# Charge_Amp_Schematic.net
KiCad netlist of a schematic drawn in Altium Designer
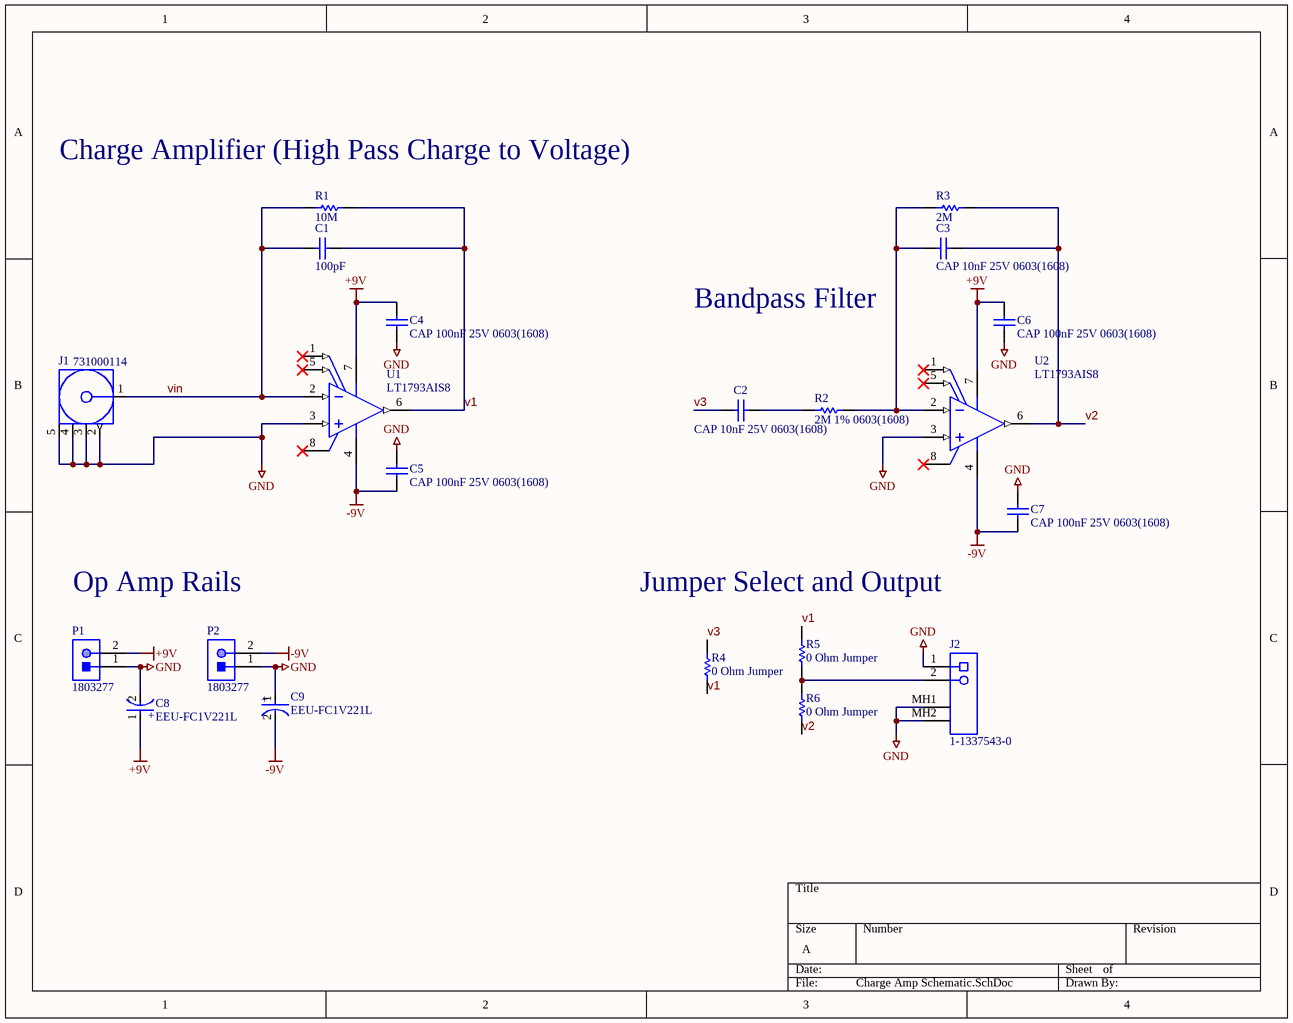
[diagram p0: Charge Amp Schematic.SchDoc]

(export (version "E")
  (design (tool "Eeschema 10.0.6"))
  (components
    (comp (ref "C1")
      (value "100pF")
      (footprint "CAPC0603(1608)100_M")
      (fields (field (name "TOLERANCE") "Â±5%"))
      (libsource (lib "Altium Content Vault") (part "CAP"))
    )
    (comp (ref "C2")
      (value "CAP 10nF 25V 0603(1608)")
      (footprint "CAPC0603(1608)100_M")
      (description "CAP 10nF 25V ±5% 0603 (1608 Metric) Thickness 1mm SMD")
      (fields (field (name "TOLERANCE") "Â±5%"))
      (libsource (lib "Altium Content Vault") (part "CAP"))
    )
    (comp (ref "C3")
      (value "CAP 10nF 25V 0603(1608)")
      (footprint "CAPC0603(1608)100_M")
      (description "CAP 10nF 25V ±5% 0603 (1608 Metric) Thickness 1mm SMD")
      (fields (field (name "TOLERANCE") "Â±5%"))
      (libsource (lib "Altium Content Vault") (part "CAP"))
    )
    (comp (ref "C4")
      (value "CAP 100nF 25V 0603(1608)")
      (footprint "CAPC0603(1608)100_N")
      (description "CAP 100nF 25V ±5% 0603 (1608 Metric) Thickness 1mm SMD")
      (fields (field (name "TOLERANCE") "Â±5%"))
      (libsource (lib "Altium Content Vault") (part "CAP"))
    )
    (comp (ref "C5")
      (value "CAP 100nF 25V 0603(1608)")
      (footprint "CAPC0603(1608)100_N")
      (description "CAP 100nF 25V ±5% 0603 (1608 Metric) Thickness 1mm SMD")
      (fields (field (name "TOLERANCE") "Â±5%"))
      (libsource (lib "Altium Content Vault") (part "CAP"))
    )
    (comp (ref "C6")
      (value "CAP 100nF 25V 0603(1608)")
      (footprint "CAPC0603(1608)100_N")
      (description "CAP 100nF 25V ±5% 0603 (1608 Metric) Thickness 1mm SMD")
      (fields (field (name "TOLERANCE") "Â±5%"))
      (libsource (lib "Altium Content Vault") (part "CAP"))
    )
    (comp (ref "C7")
      (value "CAP 100nF 25V 0603(1608)")
      (footprint "CAPC0603(1608)100_N")
      (description "CAP 100nF 25V ±5% 0603 (1608 Metric) Thickness 1mm SMD")
      (fields (field (name "TOLERANCE") "Â±5%"))
      (libsource (lib "Altium Content Vault") (part "CAP"))
    )
    (comp (ref "C8")
      (value "EEU-FC1V221L")
      (footprint "FP-EEU-FC1V221L-MFG")
      (description "CAP ALUM 220UF 20% 35V RADIAL")
      (fields
        (field (name "OCTOPART") "https://octopart.com/eeu-fc1v221l-panasonic-39478519")
        (field (name "MANUFACTURER") "Panasonic Electronic Components")
      )
      (libsource (lib "Altium Content Vault") (part "385ce6c70a3ab0aa1e866f00bd8ed49"))
    )
    (comp (ref "C9")
      (value "EEU-FC1V221L")
      (footprint "FP-EEU-FC1V221L-MFG")
      (description "CAP ALUM 220UF 20% 35V RADIAL")
      (fields
        (field (name "OCTOPART") "https://octopart.com/eeu-fc1v221l-panasonic-39478519")
        (field (name "MANUFACTURER") "Panasonic Electronic Components")
      )
      (libsource (lib "Altium Content Vault") (part "385ce6c70a3ab0aa1e866f00bd8ed49"))
    )
    (comp (ref "J1")
      (value "731000114")
      (footprint "MOLX-731000114_V")
      (description "SMA Right-Angle PCB Jack Receptacle, Brass Body, Gold Plated, 50 Ohm, 5-Pin THD, RoHS, Tray")
      (fields (field (name "MANUFACTURER") "Molex"))
      (libsource (lib "Altium Content Vault") (part "CN-S-4F-RF5"))
    )
    (comp (ref "J2")
      (value "1-1337543-0")
      (footprint "TECO-1-1337543-0_V")
      (fields (field (name "MANUFACTURER") "TE Connectivity"))
      (libsource (lib "Altium Content Vault") (part "CN-1P-F-R2_A"))
    )
    (comp (ref "P1")
      (value "1803277")
      (footprint "PHOE-1803277_V")
      (description "Male Header, Pitch 3.81 mm, 1 x 2 Position, Height 7.25 mm, Tail Length 3.4 mm, RoHS, Bulk")
      (fields (field (name "TOLERANCE") "5%"))
      (libsource (lib "Altium Content Vault") (part "CN-1P-M-R2"))
    )
    (comp (ref "P2")
      (value "1803277")
      (footprint "PHOE-1803277_V")
      (description "Male Header, Pitch 3.81 mm, 1 x 2 Position, Height 7.25 mm, Tail Length 3.4 mm, RoHS, Bulk")
      (fields (field (name "TOLERANCE") "5%"))
      (libsource (lib "Altium Content Vault") (part "CN-1P-M-R2"))
    )
    (comp (ref "R1")
      (value "10M")
      (footprint "RESC0603(1608)_M")
      (fields (field (name "TOLERANCE") "1 %") (field (name "POWER") "0.1 W"))
      (libsource (lib "Altium Content Vault") (part "RES"))
    )
    (comp (ref "R2")
      (value "2M 1% 0603(1608)")
      (footprint "RESC0603(1608)_M")
      (description "2M 0.1W 1% 0603 (1608 Metric)  SMD")
      (fields (field (name "TOLERANCE") "1 %") (field (name "POWER") "0.1 W"))
      (libsource (lib "") (part "RES_1"))
    )
    (comp (ref "R3")
      (value "2M")
      (footprint "RESC0603(1608)_M")
      (description "2M 0.1W 1% 0603 (1608 Metric)  SMD")
      (fields (field (name "TOLERANCE") "1 %") (field (name "POWER") "0.1 W"))
      (libsource (lib "Altium Content Vault") (part "RES"))
    )
    (comp (ref "R4")
      (value "0 Ohm Jumper")
      (footprint "RESC0603(1608)_L")
      (fields (field (name "TOLERANCE") "1 %") (field (name "POWER") "0.1 W"))
      (libsource (lib "Altium Content Vault") (part "RES"))
    )
    (comp (ref "R5")
      (value "0 Ohm Jumper")
      (footprint "RESC0603(1608)_L")
      (description "10R 0.1W 1% 0603 (1608 Metric)  SMD")
      (fields (field (name "TOLERANCE") "1 %") (field (name "POWER") "0.1 W"))
      (libsource (lib "Altium Content Vault") (part "RES"))
    )
    (comp (ref "R6")
      (value "0 Ohm Jumper")
      (footprint "RESC0603(1608)_L")
      (description "10R 0.1W 1% 0603 (1608 Metric)  SMD")
      (fields (field (name "TOLERANCE") "1 %") (field (name "POWER") "0.1 W"))
      (libsource (lib "Altium Content Vault") (part "RES"))
    )
    (comp (ref "U1")
      (value "LT1793AIS8")
      (footprint "LT-S8-8_M")
      (fields
        (field (name "LINEAR TECHNOLOGY PART NUMBER") "LT1793")
        (field (name "MANUFACTURER") "Linear Technology")
      )
      (libsource (lib "Altium Content Vault") (part "LT-LT179X-8"))
    )
    (comp (ref "U2")
      (value "LT1793AIS8")
      (footprint "LT-S8-8_M")
      (fields
        (field (name "LINEAR TECHNOLOGY PART NUMBER") "LT1793")
        (field (name "MANUFACTURER") "Linear Technology")
      )
      (libsource (lib "Altium Content Vault") (part "LT-LT179X-8"))
    )
  )
  (nets
    (net (code "1") (name "+9V") (class "Default")
      (node (ref "C4") (pin "2") (pinfunction "2_2") (pintype "passive"))
      (node (ref "C6") (pin "1") (pinfunction "1_1") (pintype "passive"))
      (node (ref "C8") (pin "1") (pinfunction "C_1") (pintype "passive"))
      (node (ref "P1") (pin "2") (pinfunction "2_2") (pintype "passive"))
      (node (ref "U1") (pin "7") (pinfunction "V+_7") (pintype "power_in"))
      (node (ref "U2") (pin "7") (pinfunction "V+_7") (pintype "power_in"))
    )
    (net (code "2") (name "-9V") (class "Default")
      (node (ref "C5") (pin "1") (pinfunction "1_1") (pintype "passive"))
      (node (ref "C7") (pin "2") (pinfunction "2_2") (pintype "passive"))
      (node (ref "C9") (pin "2") (pinfunction "A_2") (pintype "passive"))
      (node (ref "P2") (pin "2") (pinfunction "2_2") (pintype "passive"))
      (node (ref "U1") (pin "4") (pinfunction "V-_4") (pintype "power_in"))
      (node (ref "U2") (pin "4") (pinfunction "V-_4") (pintype "power_in"))
    )
    (net (code "3") (name "/v1") (class "Default")
      (node (ref "C1") (pin "2") (pinfunction "2_2") (pintype "passive"))
      (node (ref "R1") (pin "2") (pinfunction "2_2") (pintype "passive"))
      (node (ref "R4") (pin "1") (pinfunction "1_1") (pintype "passive"))
      (node (ref "R5") (pin "2") (pinfunction "2_2") (pintype "passive"))
      (node (ref "U1") (pin "6") (pinfunction "OUT_6") (pintype "output"))
    )
    (net (code "4") (name "/v2") (class "Default")
      (node (ref "C3") (pin "1") (pinfunction "1_1") (pintype "passive"))
      (node (ref "R3") (pin "2") (pinfunction "2_2") (pintype "passive"))
      (node (ref "R6") (pin "1") (pinfunction "1_1") (pintype "passive"))
      (node (ref "U2") (pin "6") (pinfunction "OUT_6") (pintype "output"))
    )
    (net (code "5") (name "/v3") (class "Default")
      (node (ref "C2") (pin "1") (pinfunction "1_1") (pintype "passive"))
      (node (ref "R4") (pin "2") (pinfunction "2_2") (pintype "passive"))
    )
    (net (code "6") (name "/vin") (class "Default")
      (node (ref "C1") (pin "1") (pinfunction "1_1") (pintype "passive"))
      (node (ref "J1") (pin "1") (pinfunction "1_1") (pintype "bidirectional"))
      (node (ref "R1") (pin "1") (pinfunction "1_1") (pintype "passive"))
      (node (ref "U1") (pin "2") (pinfunction "-IN_A_2") (pintype "input"))
    )
    (net (code "7") (name "GND") (class "Default")
      (node (ref "C4") (pin "1") (pinfunction "1_1") (pintype "passive"))
      (node (ref "C5") (pin "2") (pinfunction "2_2") (pintype "passive"))
      (node (ref "C6") (pin "2") (pinfunction "2_2") (pintype "passive"))
      (node (ref "C7") (pin "1") (pinfunction "1_1") (pintype "passive"))
      (node (ref "C8") (pin "2") (pinfunction "A_2") (pintype "passive"))
      (node (ref "C9") (pin "1") (pinfunction "C_1") (pintype "passive"))
      (node (ref "J1") (pin "2") (pinfunction "2_2") (pintype "output"))
      (node (ref "J1") (pin "3") (pinfunction "3_3") (pintype "passive"))
      (node (ref "J1") (pin "4") (pinfunction "4_4") (pintype "passive"))
      (node (ref "J1") (pin "5") (pinfunction "5_5") (pintype "passive"))
      (node (ref "J2") (pin "1") (pinfunction "1_1") (pintype "passive"))
      (node (ref "J2") (pin "MH1") (pinfunction "MH1_MH1") (pintype "passive"))
      (node (ref "J2") (pin "MH2") (pinfunction "MH2_MH2") (pintype "passive"))
      (node (ref "P1") (pin "1") (pinfunction "1_1") (pintype "passive"))
      (node (ref "P2") (pin "1") (pinfunction "1_1") (pintype "passive"))
      (node (ref "U1") (pin "3") (pinfunction "+IN_A_3") (pintype "input"))
      (node (ref "U2") (pin "3") (pinfunction "+IN_A_3") (pintype "input"))
    )
    (net (code "8") (name "Net-(C2-Pad2)") (class "Default")
      (node (ref "C2") (pin "2") (pinfunction "2_2") (pintype "passive"))
      (node (ref "R2") (pin "1") (pinfunction "1_1") (pintype "passive"))
    )
    (net (code "9") (name "Net-(J2-Pad2)") (class "Default")
      (node (ref "J2") (pin "2") (pinfunction "2_2") (pintype "passive"))
      (node (ref "R5") (pin "1") (pinfunction "1_1") (pintype "passive"))
      (node (ref "R6") (pin "2") (pinfunction "2_2") (pintype "passive"))
    )
    (net (code "10") (name "Net-(U2--IN_A)") (class "Default")
      (node (ref "C3") (pin "2") (pinfunction "2_2") (pintype "passive"))
      (node (ref "R2") (pin "2") (pinfunction "2_2") (pintype "bidirectional"))
      (node (ref "R3") (pin "1") (pinfunction "1_1") (pintype "passive"))
      (node (ref "U2") (pin "2") (pinfunction "-IN_A_2") (pintype "input"))
    )
    (net (code "11") (name "unconnected-(U1-NC-Pad8)") (class "Default")
      (node (ref "U1") (pin "8") (pinfunction "NC_8") (pintype "passive+no_connect"))
    )
    (net (code "12") (name "unconnected-(U1-VOS_ADJ-Pad1)") (class "Default")
      (node (ref "U1") (pin "1") (pinfunction "VOS_ADJ_1") (pintype "input+no_connect"))
    )
    (net (code "13") (name "unconnected-(U1-VOS_ADJ-Pad5)") (class "Default")
      (node (ref "U1") (pin "5") (pinfunction "VOS_ADJ_5") (pintype "input+no_connect"))
    )
    (net (code "14") (name "unconnected-(U2-NC-Pad8)") (class "Default")
      (node (ref "U2") (pin "8") (pinfunction "NC_8") (pintype "passive+no_connect"))
    )
    (net (code "15") (name "unconnected-(U2-VOS_ADJ-Pad1)") (class "Default")
      (node (ref "U2") (pin "1") (pinfunction "VOS_ADJ_1") (pintype "input+no_connect"))
    )
    (net (code "16") (name "unconnected-(U2-VOS_ADJ-Pad5)") (class "Default")
      (node (ref "U2") (pin "5") (pinfunction "VOS_ADJ_5") (pintype "input+no_connect"))
    )
  )
)
